# ADXL345_5V.net
KiCad netlist of a schematic drawn in Altium Designer
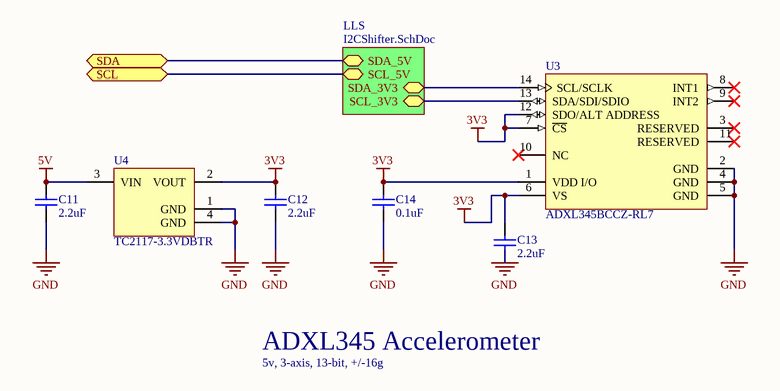
[diagram p0: ADXL345_5V.SchDoc]

(export (version "E")
  (design (tool "Eeschema 10.0.6"))
  (components
    (comp (ref "C11")
      (value "2.2uF")
      (footprint "CAPC0603(1608)100_L")
      (description "CAP 2.2uF 25V ±10% 0603 (1608 Metric) Thickness 1mm SMD")
      (fields (field (name "TOLERANCE") "Â±10%"))
      (libsource (lib "Altium Content Vault") (part "CMP-1035-02767-1"))
    )
    (comp (ref "C12")
      (value "2.2uF")
      (footprint "CAPC0603(1608)100_L")
      (description "CAP 2.2uF 25V ±10% 0603 (1608 Metric) Thickness 1mm SMD")
      (fields (field (name "TOLERANCE") "Â±10%"))
      (libsource (lib "Altium Content Vault") (part "CMP-1035-02767-1"))
    )
    (comp (ref "C13")
      (value "2.2uF")
      (footprint "CAPC0603(1608)100_L")
      (description "CAP 2.2uF 25V ±10% 0603 (1608 Metric) Thickness 1mm SMD")
      (fields (field (name "TOLERANCE") "Â±10%"))
      (libsource (lib "Altium Content Vault") (part "CMP-1035-02767-1"))
    )
    (comp (ref "C14")
      (value "0.1uF")
      (footprint "CAPC0603(1608)100_L")
      (description "CAP 100nF 50V ±5% 0603 (1608 Metric) Thickness 1mm SMD")
      (fields (field (name "TOLERANCE") "Â±5%"))
      (libsource (lib "Altium Content Vault") (part "CMP-1035-02591-1"))
    )
    (comp (ref "U3")
      (value "ADXL345BCCZ-RL7")
      (footprint "ADI-CC-14-1_V")
      (fields (field (name "MANUFACTURER") "Analog Devices"))
      (libsource (lib "Altium Content Vault") (part "ADI-ADXL34X-CC-14-1"))
    )
    (comp (ref "U4")
      (value "TC2117-3.3VDBTR")
      (footprint "SOT-223-DB3_L")
      (description "800 mA Fixed Low Dropout Positive Regulator, 3-Pin SOT-223, Extended Temperature, Tape and Reel")
      (libsource (lib "Altium Content Vault") (part "PM-LINEREG-TC2117-IL4"))
    )
  )
  (nets
    (net (code "2") (name "/SCL_3V3") (class "Default")
      (node (ref "U3") (pin "13") (pinfunction "SDA/SDI/SDIO_13") (pintype "bidirectional"))
    )
    (net (code "4") (name "/SDA_3V3") (class "Default")
      (node (ref "U3") (pin "14") (pinfunction "SCL/SCLK_14") (pintype "input"))
    )
    (net (code "5") (name "3V3") (class "Default")
      (node (ref "C12") (pin "2") (pinfunction "2_2") (pintype "passive"))
      (node (ref "C13") (pin "2") (pinfunction "2_2") (pintype "passive"))
      (node (ref "C14") (pin "2") (pinfunction "2_2") (pintype "passive"))
      (node (ref "U3") (pin "1") (pinfunction "VDD_I/O_1") (pintype "power_in"))
      (node (ref "U3") (pin "12") (pinfunction "SDO/ALT_ADDRESS_12") (pintype "bidirectional"))
      (node (ref "U3") (pin "6") (pinfunction "VS_6") (pintype "power_in"))
      (node (ref "U3") (pin "7") (pinfunction "~{CS}_7") (pintype "input"))
      (node (ref "U4") (pin "2") (pinfunction "VOUT_2") (pintype "power_in"))
    )
    (net (code "6") (name "5V") (class "Default")
      (node (ref "C11") (pin "2") (pinfunction "2_2") (pintype "passive"))
      (node (ref "U4") (pin "3") (pinfunction "VIN_3") (pintype "power_in"))
    )
    (net (code "7") (name "GND") (class "Default")
      (node (ref "C11") (pin "1") (pinfunction "1_1") (pintype "passive"))
      (node (ref "C12") (pin "1") (pinfunction "1_1") (pintype "passive"))
      (node (ref "C13") (pin "1") (pinfunction "1_1") (pintype "passive"))
      (node (ref "C14") (pin "1") (pinfunction "1_1") (pintype "passive"))
      (node (ref "U3") (pin "2") (pinfunction "GND_2") (pintype "power_in"))
      (node (ref "U3") (pin "4") (pinfunction "GND_4") (pintype "power_in"))
      (node (ref "U3") (pin "5") (pinfunction "GND_5") (pintype "power_in"))
      (node (ref "U4") (pin "1") (pinfunction "GND_1") (pintype "power_in"))
      (node (ref "U4") (pin "4") (pinfunction "GND_4") (pintype "power_in"))
    )
    (net (code "8") (name "unconnected-(U3-INT1-Pad8)") (class "Default")
      (node (ref "U3") (pin "8") (pinfunction "INT1_8") (pintype "output+no_connect"))
    )
    (net (code "9") (name "unconnected-(U3-INT2-Pad9)") (class "Default")
      (node (ref "U3") (pin "9") (pinfunction "INT2_9") (pintype "output+no_connect"))
    )
    (net (code "10") (name "unconnected-(U3-NC-Pad10)") (class "Default")
      (node (ref "U3") (pin "10") (pinfunction "NC_10") (pintype "passive+no_connect"))
    )
    (net (code "11") (name "unconnected-(U3-RESERVED-Pad3)") (class "Default")
      (node (ref "U3") (pin "3") (pinfunction "RESERVED_3") (pintype "passive+no_connect"))
    )
    (net (code "12") (name "unconnected-(U3-RESERVED-Pad11)") (class "Default")
      (node (ref "U3") (pin "11") (pinfunction "RESERVED_11") (pintype "passive+no_connect"))
    )
  )
)
